# Microcontroller.net
KiCad netlist of a schematic drawn in Altium Designer
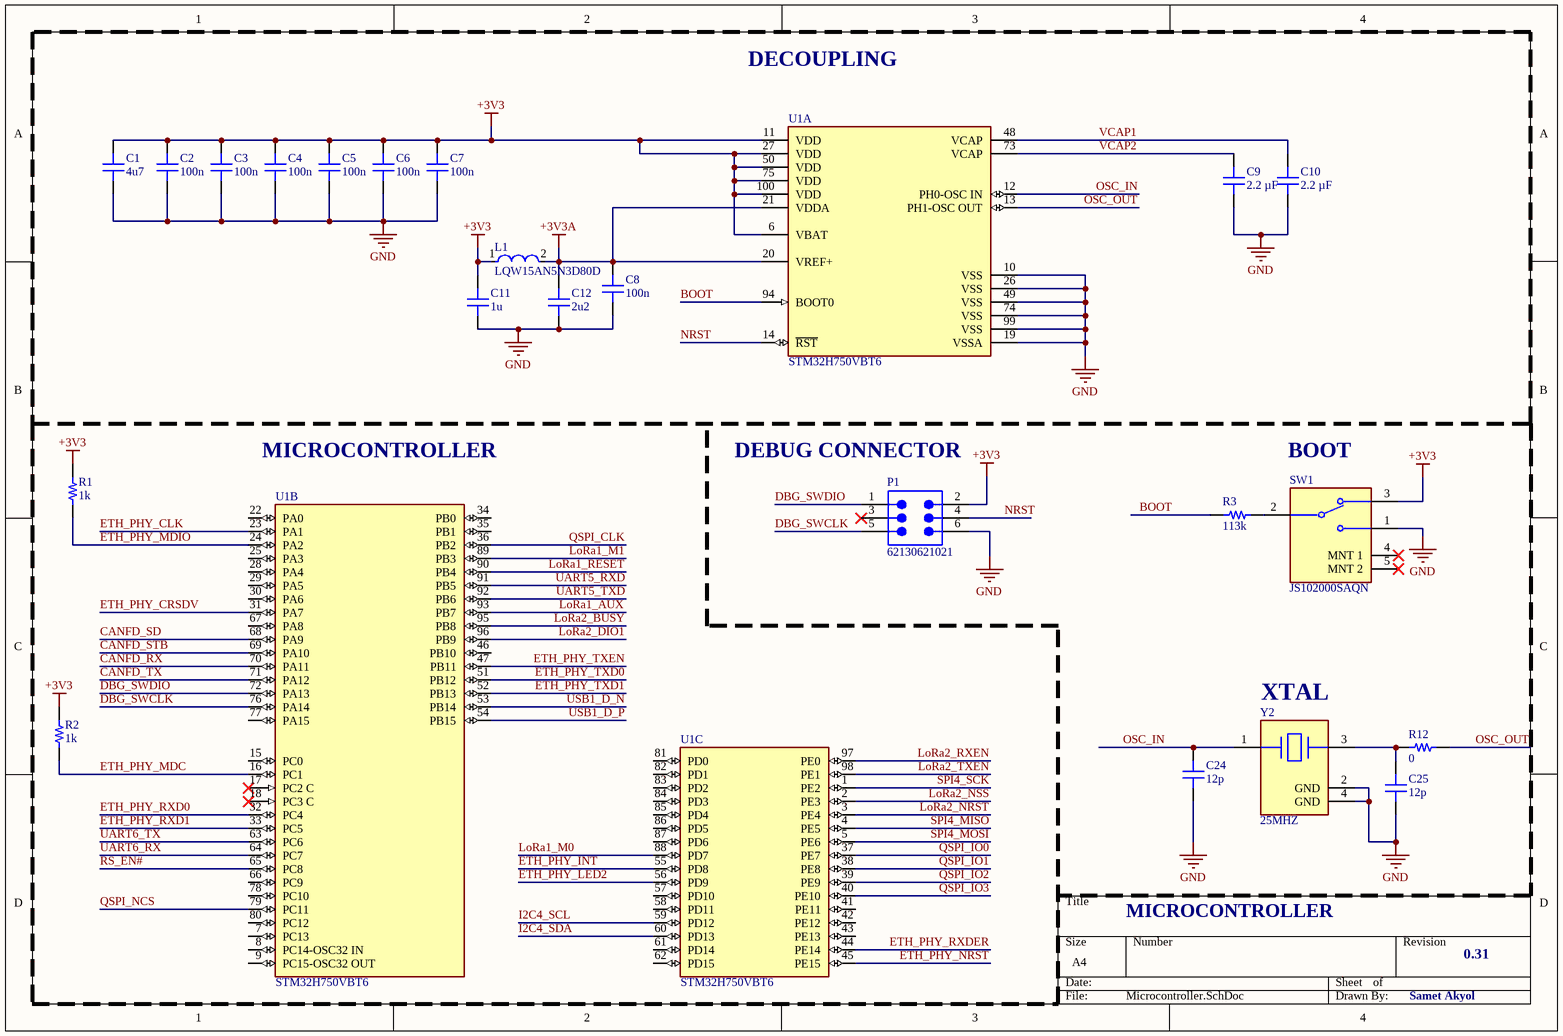
[diagram p0: Microcontroller.SchDoc]

(export (version "E")
  (design (tool "Eeschema 10.0.6"))
  (components
    (comp (ref "C1")
      (value "4u7")
      (footprint "CAP 0402_1005")
      (description "CAP CER 100NF 10V X7R 0402")
      (fields
        (field (name "PART NUMBER") "CL05B104KP5VPNC")
        (field (name "MANUFACTURER") "Samsung Electro-Mechanics")
      )
      (libsource (lib "Celestial Altium Library - altium_library") (part "Capacitor"))
    )
    (comp (ref "C2")
      (value "100n")
      (footprint "CAP 0402_1005")
      (description "CAP CER 100NF 10V X7R 0402")
      (fields
        (field (name "PART NUMBER") "CL05B104KP5VPNC")
        (field (name "MANUFACTURER") "Samsung Electro-Mechanics")
      )
      (libsource (lib "Celestial Altium Library - altium_library") (part "Capacitor"))
    )
    (comp (ref "C3")
      (value "100n")
      (footprint "CAP 0402_1005")
      (description "CAP CER 100NF 10V X7R 0402")
      (fields
        (field (name "PART NUMBER") "CL05B104KP5VPNC")
        (field (name "MANUFACTURER") "Samsung Electro-Mechanics")
      )
      (libsource (lib "Celestial Altium Library - altium_library") (part "Capacitor"))
    )
    (comp (ref "C4")
      (value "100n")
      (footprint "CAP 0402_1005")
      (description "CAP CER 100NF 10V X7R 0402")
      (fields
        (field (name "PART NUMBER") "CL05B104KP5VPNC")
        (field (name "MANUFACTURER") "Samsung Electro-Mechanics")
      )
      (libsource (lib "Celestial Altium Library - altium_library") (part "Capacitor"))
    )
    (comp (ref "C5")
      (value "100n")
      (footprint "CAP 0402_1005")
      (description "CAP CER 100NF 10V X7R 0402")
      (fields
        (field (name "PART NUMBER") "CL05B104KP5VPNC")
        (field (name "MANUFACTURER") "Samsung Electro-Mechanics")
      )
      (libsource (lib "Celestial Altium Library - altium_library") (part "Capacitor"))
    )
    (comp (ref "C6")
      (value "100n")
      (footprint "CAP 0402_1005")
      (description "CAP CER 100NF 10V X7R 0402")
      (fields
        (field (name "PART NUMBER") "CL05B104KP5VPNC")
        (field (name "MANUFACTURER") "Samsung Electro-Mechanics")
      )
      (libsource (lib "Celestial Altium Library - altium_library") (part "Capacitor"))
    )
    (comp (ref "C7")
      (value "100n")
      (footprint "CAP 0402_1005")
      (description "CAP CER 100NF 10V X7R 0402")
      (fields
        (field (name "PART NUMBER") "CL05B104KP5VPNC")
        (field (name "MANUFACTURER") "Samsung Electro-Mechanics")
      )
      (libsource (lib "Celestial Altium Library - altium_library") (part "Capacitor"))
    )
    (comp (ref "C8")
      (value "100n")
      (footprint "CAP 0402_1005")
      (description "CAP CER 100NF 10V X7R 0402")
      (fields
        (field (name "PART NUMBER") "CL05B104KP5VPNC")
        (field (name "MANUFACTURER") "Samsung Electro-Mechanics")
      )
      (libsource (lib "Celestial Altium Library - altium_library") (part "Capacitor"))
    )
    (comp (ref "C9")
      (value "2.2 µF")
      (footprint "CAP 0402_1005")
      (description "CAP CER 2.2UF 16V X5R 0402")
      (fields
        (field (name "PART NUMBER") "CL05A225KO5NQNC")
        (field (name "MANUFACTURER") "Samsung Electro-Mechanics")
      )
      (libsource (lib "Celestial Altium Library - altium_library") (part "Capacitor"))
    )
    (comp (ref "C10")
      (value "2.2 µF")
      (footprint "CAP 0402_1005")
      (description "CAP CER 2.2UF 16V X5R 0402")
      (fields
        (field (name "PART NUMBER") "CL05A225KO5NQNC")
        (field (name "MANUFACTURER") "Samsung Electro-Mechanics")
      )
      (libsource (lib "Celestial Altium Library - altium_library") (part "Capacitor"))
    )
    (comp (ref "C11")
      (value "1u")
      (footprint "CAP 0402_1005")
      (description "CAP CER 100NF 10V X7R 0402")
      (fields
        (field (name "PART NUMBER") "CL05B104KP5VPNC")
        (field (name "MANUFACTURER") "Samsung Electro-Mechanics")
      )
      (libsource (lib "Celestial Altium Library - altium_library") (part "Capacitor"))
    )
    (comp (ref "C12")
      (value "2u2")
      (footprint "CAP 0402_1005")
      (description "CAP CER 100NF 10V X7R 0402")
      (fields
        (field (name "PART NUMBER") "CL05B104KP5VPNC")
        (field (name "MANUFACTURER") "Samsung Electro-Mechanics")
      )
      (libsource (lib "Celestial Altium Library - altium_library") (part "Capacitor"))
    )
    (comp (ref "C24")
      (value "12p")
      (footprint "CAP 0402_1005")
      (description "CAP CER 100NF 10V X7R 0402")
      (fields
        (field (name "PART NUMBER") "CL05B104KP5VPNC")
        (field (name "MANUFACTURER") "Samsung Electro-Mechanics")
      )
      (libsource (lib "Celestial Altium Library - altium_library") (part "Capacitor"))
    )
    (comp (ref "C25")
      (value "12p")
      (footprint "CAP 0402_1005")
      (description "CAP CER 100NF 10V X7R 0402")
      (fields
        (field (name "PART NUMBER") "CL05B104KP5VPNC")
        (field (name "MANUFACTURER") "Samsung Electro-Mechanics")
      )
      (libsource (lib "Celestial Altium Library - altium_library") (part "Capacitor"))
    )
    (comp (ref "L1")
      (value "LQW15AN5N3D80D")
      (footprint "FP-LQW15AN_80-MFG")
      (description "Wire Wound RF Inductor 5.3nH ±0.5nH 1770mA 0.04Ω 0402 (1005)")
      (libsource (lib "Altium Content Vault") (part "725321dda6339637d4d059423bc1c3c"))
    )
    (comp (ref "P1")
      (value "62130621021")
      (footprint "62130621021")
      (libsource (lib "Altium Content Vault") (part "Header_Male_2R_06P"))
    )
    (comp (ref "R1")
      (value "1k")
      (footprint "RES 0402_1005")
      (description "RES 249K OHM 0.1% 1/10W 0402")
      (fields
        (field (name "PART NUMBER") "RP73PF1E249KBTD")
        (field (name "MANUFACTURER") "TE Connectivity Passive Product")
      )
      (libsource (lib "Celestial Altium Library - altium_library") (part "Resistor"))
    )
    (comp (ref "R2")
      (value "1k")
      (footprint "RES 0402_1005")
      (description "RES 249K OHM 0.1% 1/10W 0402")
      (fields
        (field (name "PART NUMBER") "RP73PF1E249KBTD")
        (field (name "MANUFACTURER") "TE Connectivity Passive Product")
      )
      (libsource (lib "Celestial Altium Library - altium_library") (part "Resistor"))
    )
    (comp (ref "R3")
      (value "113k")
      (footprint "RES 0402_1005")
      (description "RES 249K OHM 0.1% 1/10W 0402")
      (fields
        (field (name "PART NUMBER") "RP73PF1E249KBTD")
        (field (name "MANUFACTURER") "TE Connectivity Passive Product")
      )
      (libsource (lib "Celestial Altium Library - altium_library") (part "Resistor"))
    )
    (comp (ref "R12")
      (value "0")
      (footprint "RES 0402_1005")
      (description "RES 249K OHM 0.1% 1/10W 0402")
      (fields
        (field (name "PART NUMBER") "RP73PF1E249KBTD")
        (field (name "MANUFACTURER") "TE Connectivity Passive Product")
      )
      (libsource (lib "Celestial Altium Library - altium_library") (part "Resistor"))
    )
    (comp (ref "SW1")
      (value "JS102000SAQN")
      (footprint "FP-JS102000SAQN-MFG")
      (description "SWITCH SLIDE SPDT 1MA 5V")
      (libsource (lib "Altium Content Vault") (part "6887e5fe807d9c5c2853bed39bc55bf"))
    )
    (comp (ref "U1")
      (value "STM32H750VBT6")
      (footprint "FP-LQFP100-1L-MFG")
      (description "IC MCU 32BIT 128KB FLASH 100LQFP")
      (fields
        (field (name "OCTOPART") "https://octopart.com/stm32h750vbt6-stmicroelectronics-94048547")
        (field (name "MANUFACTURER") "STMicroelectronics")
      )
      (libsource (lib "Altium Content Vault") (part "aca449acb2b80670ba40d015d68dc7a"))
    )
    (comp (ref "Y2")
      (value "25MHZ")
      (footprint "FP-ABM8G-MFG")
      (description "Crystal 25MHz ±20ppm (Tol) ±30ppm (Stability) 18pF FUND 60Ω 4-Pin SMD T/R")
      (fields (field (name "TOLERANCE") "20ppm"))
      (libsource (lib "Altium Content Vault") (part "48e526d86b7f2615d98721063c72f49"))
    )
  )
  (nets
    (net (code "1") (name "+3V3") (class "Default")
      (node (ref "C1") (pin "2") (pinfunction "2_2") (pintype "passive"))
      (node (ref "C11") (pin "2") (pinfunction "2_2") (pintype "passive"))
      (node (ref "C2") (pin "2") (pinfunction "2_2") (pintype "passive"))
      (node (ref "C3") (pin "2") (pinfunction "2_2") (pintype "passive"))
      (node (ref "C4") (pin "2") (pinfunction "2_2") (pintype "passive"))
      (node (ref "C5") (pin "2") (pinfunction "2_2") (pintype "passive"))
      (node (ref "C6") (pin "2") (pinfunction "2_2") (pintype "passive"))
      (node (ref "C7") (pin "2") (pinfunction "2_2") (pintype "passive"))
      (node (ref "L1") (pin "1") (pinfunction "1_1") (pintype "passive"))
      (node (ref "P1") (pin "2") (pinfunction "2_2") (pintype "passive"))
      (node (ref "R1") (pin "1") (pinfunction "1_1") (pintype "passive"))
      (node (ref "R2") (pin "1") (pinfunction "1_1") (pintype "passive"))
      (node (ref "SW1") (pin "3") (pinfunction "3_3") (pintype "passive"))
      (node (ref "U1") (pin "100") (pinfunction "VDD_100") (pintype "power_in"))
      (node (ref "U1") (pin "11") (pinfunction "VDD_11") (pintype "power_in"))
      (node (ref "U1") (pin "27") (pinfunction "VDD_27") (pintype "power_in"))
      (node (ref "U1") (pin "50") (pinfunction "VDD_50") (pintype "power_in"))
      (node (ref "U1") (pin "6") (pinfunction "VBAT_6") (pintype "power_in"))
      (node (ref "U1") (pin "75") (pinfunction "VDD_75") (pintype "power_in"))
    )
    (net (code "2") (name "+3V3A") (class "Default")
      (node (ref "C12") (pin "2") (pinfunction "2_2") (pintype "passive"))
      (node (ref "C8") (pin "2") (pinfunction "2_2") (pintype "passive"))
      (node (ref "L1") (pin "2") (pinfunction "2_2") (pintype "passive"))
      (node (ref "U1") (pin "20") (pinfunction "VREF+_20") (pintype "power_in"))
      (node (ref "U1") (pin "21") (pinfunction "VDDA_21") (pintype "power_in"))
    )
    (net (code "3") (name "/BOOT") (class "Default")
      (node (ref "R3") (pin "2") (pinfunction "2_2") (pintype "passive"))
      (node (ref "U1") (pin "94") (pinfunction "BOOT0_94") (pintype "input"))
    )
    (net (code "4") (name "/CANFD_RX") (class "Default")
      (node (ref "U1") (pin "70") (pinfunction "PA11_70") (pintype "bidirectional"))
    )
    (net (code "5") (name "/CANFD_SD") (class "Default")
      (node (ref "U1") (pin "68") (pinfunction "PA9_68") (pintype "bidirectional"))
    )
    (net (code "6") (name "/CANFD_STB") (class "Default")
      (node (ref "U1") (pin "69") (pinfunction "PA10_69") (pintype "bidirectional"))
    )
    (net (code "7") (name "/CANFD_TX") (class "Default")
      (node (ref "U1") (pin "71") (pinfunction "PA12_71") (pintype "bidirectional"))
    )
    (net (code "8") (name "/DBG_SWCLK") (class "Default")
      (node (ref "P1") (pin "5") (pinfunction "5_5") (pintype "passive"))
      (node (ref "U1") (pin "76") (pinfunction "PA14_76") (pintype "bidirectional"))
    )
    (net (code "9") (name "/DBG_SWDIO") (class "Default")
      (node (ref "P1") (pin "1") (pinfunction "1_1") (pintype "passive"))
      (node (ref "U1") (pin "72") (pinfunction "PA13_72") (pintype "bidirectional"))
    )
    (net (code "10") (name "/ETH_PHY_CLK") (class "Default")
      (node (ref "U1") (pin "23") (pinfunction "PA1_23") (pintype "bidirectional"))
    )
    (net (code "11") (name "/ETH_PHY_CRSDV") (class "Default")
      (node (ref "U1") (pin "31") (pinfunction "PA7_31") (pintype "bidirectional"))
    )
    (net (code "12") (name "/ETH_PHY_INT") (class "Default")
      (node (ref "U1") (pin "55") (pinfunction "PD8_55") (pintype "bidirectional"))
    )
    (net (code "13") (name "/ETH_PHY_LED2") (class "Default")
      (node (ref "U1") (pin "56") (pinfunction "PD9_56") (pintype "bidirectional"))
    )
    (net (code "14") (name "/ETH_PHY_MDC") (class "Default")
      (node (ref "R2") (pin "2") (pinfunction "2_2") (pintype "passive"))
      (node (ref "U1") (pin "16") (pinfunction "PC1_16") (pintype "bidirectional"))
    )
    (net (code "15") (name "/ETH_PHY_MDIO") (class "Default")
      (node (ref "R1") (pin "2") (pinfunction "2_2") (pintype "passive"))
      (node (ref "U1") (pin "24") (pinfunction "PA2_24") (pintype "bidirectional"))
    )
    (net (code "16") (name "/ETH_PHY_NRST") (class "Default")
      (node (ref "U1") (pin "45") (pinfunction "PE15_45") (pintype "bidirectional"))
    )
    (net (code "17") (name "/ETH_PHY_RXD0") (class "Default")
      (node (ref "U1") (pin "32") (pinfunction "PC4_32") (pintype "bidirectional"))
    )
    (net (code "18") (name "/ETH_PHY_RXD1") (class "Default")
      (node (ref "U1") (pin "33") (pinfunction "PC5_33") (pintype "bidirectional"))
    )
    (net (code "19") (name "/ETH_PHY_RXDER") (class "Default")
      (node (ref "U1") (pin "44") (pinfunction "PE14_44") (pintype "bidirectional"))
    )
    (net (code "20") (name "/ETH_PHY_TXD0") (class "Default")
      (node (ref "U1") (pin "51") (pinfunction "PB12_51") (pintype "bidirectional"))
    )
    (net (code "21") (name "/ETH_PHY_TXD1") (class "Default")
      (node (ref "U1") (pin "52") (pinfunction "PB13_52") (pintype "bidirectional"))
    )
    (net (code "22") (name "/ETH_PHY_TXEN") (class "Default")
      (node (ref "U1") (pin "47") (pinfunction "PB11_47") (pintype "bidirectional"))
    )
    (net (code "23") (name "/I2C4_SCL") (class "Default")
      (node (ref "U1") (pin "59") (pinfunction "PD12_59") (pintype "bidirectional"))
    )
    (net (code "24") (name "/I2C4_SDA") (class "Default")
      (node (ref "U1") (pin "60") (pinfunction "PD13_60") (pintype "bidirectional"))
    )
    (net (code "25") (name "/LoRa1_AUX") (class "Default")
      (node (ref "U1") (pin "93") (pinfunction "PB7_93") (pintype "bidirectional"))
    )
    (net (code "26") (name "/LoRa1_M0") (class "Default")
      (node (ref "U1") (pin "88") (pinfunction "PD7_88") (pintype "bidirectional"))
    )
    (net (code "27") (name "/LoRa1_M1") (class "Default")
      (node (ref "U1") (pin "89") (pinfunction "PB3_89") (pintype "bidirectional"))
    )
    (net (code "28") (name "/LoRa1_RESET") (class "Default")
      (node (ref "U1") (pin "90") (pinfunction "PB4_90") (pintype "bidirectional"))
    )
    (net (code "29") (name "/LoRa2_BUSY") (class "Default")
      (node (ref "U1") (pin "95") (pinfunction "PB8_95") (pintype "bidirectional"))
    )
    (net (code "30") (name "/LoRa2_DIO1") (class "Default")
      (node (ref "U1") (pin "96") (pinfunction "PB9_96") (pintype "bidirectional"))
    )
    (net (code "31") (name "/LoRa2_NRST") (class "Default")
      (node (ref "U1") (pin "3") (pinfunction "PE4_3") (pintype "bidirectional"))
    )
    (net (code "32") (name "/LoRa2_NSS") (class "Default")
      (node (ref "U1") (pin "2") (pinfunction "PE3_2") (pintype "bidirectional"))
    )
    (net (code "33") (name "/LoRa2_RXEN") (class "Default")
      (node (ref "U1") (pin "97") (pinfunction "PE0_97") (pintype "bidirectional"))
    )
    (net (code "34") (name "/LoRa2_TXEN") (class "Default")
      (node (ref "U1") (pin "98") (pinfunction "PE1_98") (pintype "bidirectional"))
    )
    (net (code "35") (name "/NRST") (class "Default")
      (node (ref "P1") (pin "4") (pinfunction "4_4") (pintype "passive"))
      (node (ref "U1") (pin "14") (pinfunction "~{RST}_14") (pintype "bidirectional"))
    )
    (net (code "36") (name "/OSC_IN") (class "Default")
      (node (ref "C24") (pin "2") (pinfunction "2_2") (pintype "passive"))
      (node (ref "U1") (pin "12") (pinfunction "PH0-OSC_IN_12") (pintype "bidirectional"))
      (node (ref "Y2") (pin "1") (pinfunction "1_1") (pintype "passive"))
    )
    (net (code "37") (name "/OSC_OUT") (class "Default")
      (node (ref "R12") (pin "1") (pinfunction "1_1") (pintype "passive"))
      (node (ref "U1") (pin "13") (pinfunction "PH1-OSC_OUT_13") (pintype "bidirectional"))
    )
    (net (code "38") (name "/QSPI_CLK") (class "Default")
      (node (ref "U1") (pin "36") (pinfunction "PB2_36") (pintype "bidirectional"))
    )
    (net (code "39") (name "/QSPI_IO0") (class "Default")
      (node (ref "U1") (pin "37") (pinfunction "PE7_37") (pintype "bidirectional"))
    )
    (net (code "40") (name "/QSPI_IO1") (class "Default")
      (node (ref "U1") (pin "38") (pinfunction "PE8_38") (pintype "bidirectional"))
    )
    (net (code "41") (name "/QSPI_IO2") (class "Default")
      (node (ref "U1") (pin "39") (pinfunction "PE9_39") (pintype "bidirectional"))
    )
    (net (code "42") (name "/QSPI_IO3") (class "Default")
      (node (ref "U1") (pin "40") (pinfunction "PE10_40") (pintype "bidirectional"))
    )
    (net (code "43") (name "/QSPI_NCS") (class "Default")
      (node (ref "U1") (pin "79") (pinfunction "PC11_79") (pintype "bidirectional"))
    )
    (net (code "44") (name "/RS_EN#") (class "Default")
      (node (ref "U1") (pin "65") (pinfunction "PC8_65") (pintype "bidirectional"))
    )
    (net (code "45") (name "/SPI4_MISO") (class "Default")
      (node (ref "U1") (pin "4") (pinfunction "PE5_4") (pintype "bidirectional"))
    )
    (net (code "46") (name "/SPI4_MOSI") (class "Default")
      (node (ref "U1") (pin "5") (pinfunction "PE6_5") (pintype "bidirectional"))
    )
    (net (code "47") (name "/SPI4_SCK") (class "Default")
      (node (ref "U1") (pin "1") (pinfunction "PE2_1") (pintype "bidirectional"))
    )
    (net (code "48") (name "/UART5_RXD") (class "Default")
      (node (ref "U1") (pin "91") (pinfunction "PB5_91") (pintype "bidirectional"))
    )
    (net (code "49") (name "/UART5_TXD") (class "Default")
      (node (ref "U1") (pin "92") (pinfunction "PB6_92") (pintype "bidirectional"))
    )
    (net (code "50") (name "/UART6_RX") (class "Default")
      (node (ref "U1") (pin "64") (pinfunction "PC7_64") (pintype "bidirectional"))
    )
    (net (code "51") (name "/UART6_TX") (class "Default")
      (node (ref "U1") (pin "63") (pinfunction "PC6_63") (pintype "bidirectional"))
    )
    (net (code "52") (name "/USB1_D_N") (class "Default")
      (node (ref "U1") (pin "53") (pinfunction "PB14_53") (pintype "bidirectional"))
    )
    (net (code "53") (name "/USB1_D_P") (class "Default")
      (node (ref "U1") (pin "54") (pinfunction "PB15_54") (pintype "bidirectional"))
    )
    (net (code "54") (name "/VCAP1") (class "Default")
      (node (ref "C10") (pin "2") (pinfunction "2_2") (pintype "passive"))
      (node (ref "U1") (pin "48") (pinfunction "VCAP_48") (pintype "power_in"))
    )
    (net (code "55") (name "/VCAP2") (class "Default")
      (node (ref "C9") (pin "2") (pinfunction "2_2") (pintype "passive"))
      (node (ref "U1") (pin "73") (pinfunction "VCAP_73") (pintype "power_in"))
    )
    (net (code "56") (name "GND") (class "Default")
      (node (ref "C1") (pin "1") (pinfunction "1_1") (pintype "passive"))
      (node (ref "C10") (pin "1") (pinfunction "1_1") (pintype "passive"))
      (node (ref "C11") (pin "1") (pinfunction "1_1") (pintype "passive"))
      (node (ref "C12") (pin "1") (pinfunction "1_1") (pintype "passive"))
      (node (ref "C2") (pin "1") (pinfunction "1_1") (pintype "passive"))
      (node (ref "C24") (pin "1") (pinfunction "1_1") (pintype "passive"))
      (node (ref "C25") (pin "1") (pinfunction "1_1") (pintype "passive"))
      (node (ref "C3") (pin "1") (pinfunction "1_1") (pintype "passive"))
      (node (ref "C4") (pin "1") (pinfunction "1_1") (pintype "passive"))
      (node (ref "C5") (pin "1") (pinfunction "1_1") (pintype "passive"))
      (node (ref "C6") (pin "1") (pinfunction "1_1") (pintype "passive"))
      (node (ref "C7") (pin "1") (pinfunction "1_1") (pintype "passive"))
      (node (ref "C8") (pin "1") (pinfunction "1_1") (pintype "passive"))
      (node (ref "C9") (pin "1") (pinfunction "1_1") (pintype "passive"))
      (node (ref "P1") (pin "6") (pinfunction "6_6") (pintype "passive"))
      (node (ref "SW1") (pin "1") (pinfunction "1_1") (pintype "passive"))
      (node (ref "U1") (pin "10") (pinfunction "VSS_10") (pintype "power_in"))
      (node (ref "U1") (pin "19") (pinfunction "VSSA_19") (pintype "power_in"))
      (node (ref "U1") (pin "26") (pinfunction "VSS_26") (pintype "power_in"))
      (node (ref "U1") (pin "49") (pinfunction "VSS_49") (pintype "power_in"))
      (node (ref "U1") (pin "74") (pinfunction "VSS_74") (pintype "power_in"))
      (node (ref "U1") (pin "99") (pinfunction "VSS_99") (pintype "power_in"))
      (node (ref "Y2") (pin "2") (pinfunction "GND_2") (pintype "power_in"))
      (node (ref "Y2") (pin "4") (pinfunction "GND_4") (pintype "power_in"))
    )
    (net (code "57") (name "Net-(C25-Pad2)") (class "Default")
      (node (ref "C25") (pin "2") (pinfunction "2_2") (pintype "passive"))
      (node (ref "R12") (pin "2") (pinfunction "2_2") (pintype "passive"))
      (node (ref "Y2") (pin "3") (pinfunction "3_3") (pintype "passive"))
    )
    (net (code "58") (name "Net-(SW1-C)") (class "Default")
      (node (ref "R3") (pin "1") (pinfunction "1_1") (pintype "passive"))
      (node (ref "SW1") (pin "2") (pinfunction "C_2") (pintype "passive"))
    )
    (net (code "59") (name "unconnected-(P1-Pad3)") (class "Default")
      (node (ref "P1") (pin "3") (pinfunction "3_3") (pintype "passive+no_connect"))
    )
    (net (code "60") (name "unconnected-(SW1-MNT_1-Pad4)") (class "Default")
      (node (ref "SW1") (pin "4") (pinfunction "MNT_1_4") (pintype "passive+no_connect"))
    )
    (net (code "61") (name "unconnected-(SW1-MNT_2-Pad5)") (class "Default")
      (node (ref "SW1") (pin "5") (pinfunction "MNT_2_5") (pintype "passive+no_connect"))
    )
    (net (code "62") (name "unconnected-(U1B-PA0-Pad22)") (class "Default")
      (node (ref "U1") (pin "22") (pinfunction "PA0_22") (pintype "bidirectional"))
    )
    (net (code "63") (name "unconnected-(U1B-PA3-Pad25)") (class "Default")
      (node (ref "U1") (pin "25") (pinfunction "PA3_25") (pintype "bidirectional"))
    )
    (net (code "64") (name "unconnected-(U1B-PA4-Pad28)") (class "Default")
      (node (ref "U1") (pin "28") (pinfunction "PA4_28") (pintype "bidirectional"))
    )
    (net (code "65") (name "unconnected-(U1B-PA5-Pad29)") (class "Default")
      (node (ref "U1") (pin "29") (pinfunction "PA5_29") (pintype "bidirectional"))
    )
    (net (code "66") (name "unconnected-(U1B-PA6-Pad30)") (class "Default")
      (node (ref "U1") (pin "30") (pinfunction "PA6_30") (pintype "bidirectional"))
    )
    (net (code "67") (name "unconnected-(U1B-PA8-Pad67)") (class "Default")
      (node (ref "U1") (pin "67") (pinfunction "PA8_67") (pintype "bidirectional"))
    )
    (net (code "68") (name "unconnected-(U1B-PA15-Pad77)") (class "Default")
      (node (ref "U1") (pin "77") (pinfunction "PA15_77") (pintype "bidirectional"))
    )
    (net (code "69") (name "unconnected-(U1B-PB0-Pad34)") (class "Default")
      (node (ref "U1") (pin "34") (pinfunction "PB0_34") (pintype "bidirectional"))
    )
    (net (code "70") (name "unconnected-(U1B-PB1-Pad35)") (class "Default")
      (node (ref "U1") (pin "35") (pinfunction "PB1_35") (pintype "bidirectional"))
    )
    (net (code "71") (name "unconnected-(U1B-PB10-Pad46)") (class "Default")
      (node (ref "U1") (pin "46") (pinfunction "PB10_46") (pintype "bidirectional"))
    )
    (net (code "72") (name "unconnected-(U1B-PC0-Pad15)") (class "Default")
      (node (ref "U1") (pin "15") (pinfunction "PC0_15") (pintype "bidirectional"))
    )
    (net (code "73") (name "unconnected-(U1B-PC2_C-Pad17)") (class "Default")
      (node (ref "U1") (pin "17") (pinfunction "PC2_C_17") (pintype "input+no_connect"))
    )
    (net (code "74") (name "unconnected-(U1B-PC3_C-Pad18)") (class "Default")
      (node (ref "U1") (pin "18") (pinfunction "PC3_C_18") (pintype "input+no_connect"))
    )
    (net (code "75") (name "unconnected-(U1B-PC9-Pad66)") (class "Default")
      (node (ref "U1") (pin "66") (pinfunction "PC9_66") (pintype "bidirectional"))
    )
    (net (code "76") (name "unconnected-(U1B-PC10-Pad78)") (class "Default")
      (node (ref "U1") (pin "78") (pinfunction "PC10_78") (pintype "bidirectional"))
    )
    (net (code "77") (name "unconnected-(U1B-PC12-Pad80)") (class "Default")
      (node (ref "U1") (pin "80") (pinfunction "PC12_80") (pintype "bidirectional"))
    )
    (net (code "78") (name "unconnected-(U1B-PC13-Pad7)") (class "Default")
      (node (ref "U1") (pin "7") (pinfunction "PC13_7") (pintype "bidirectional"))
    )
    (net (code "79") (name "unconnected-(U1B-PC14-OSC32_IN-Pad8)") (class "Default")
      (node (ref "U1") (pin "8") (pinfunction "PC14-OSC32_IN_8") (pintype "bidirectional"))
    )
    (net (code "80") (name "unconnected-(U1B-PC15-OSC32_OUT-Pad9)") (class "Default")
      (node (ref "U1") (pin "9") (pinfunction "PC15-OSC32_OUT_9") (pintype "bidirectional"))
    )
    (net (code "81") (name "unconnected-(U1C-PD0-Pad81)") (class "Default")
      (node (ref "U1") (pin "81") (pinfunction "PD0_81") (pintype "bidirectional"))
    )
    (net (code "82") (name "unconnected-(U1C-PD1-Pad82)") (class "Default")
      (node (ref "U1") (pin "82") (pinfunction "PD1_82") (pintype "bidirectional"))
    )
    (net (code "83") (name "unconnected-(U1C-PD2-Pad83)") (class "Default")
      (node (ref "U1") (pin "83") (pinfunction "PD2_83") (pintype "bidirectional"))
    )
    (net (code "84") (name "unconnected-(U1C-PD3-Pad84)") (class "Default")
      (node (ref "U1") (pin "84") (pinfunction "PD3_84") (pintype "bidirectional"))
    )
    (net (code "85") (name "unconnected-(U1C-PD4-Pad85)") (class "Default")
      (node (ref "U1") (pin "85") (pinfunction "PD4_85") (pintype "bidirectional"))
    )
    (net (code "86") (name "unconnected-(U1C-PD5-Pad86)") (class "Default")
      (node (ref "U1") (pin "86") (pinfunction "PD5_86") (pintype "bidirectional"))
    )
    (net (code "87") (name "unconnected-(U1C-PD6-Pad87)") (class "Default")
      (node (ref "U1") (pin "87") (pinfunction "PD6_87") (pintype "bidirectional"))
    )
    (net (code "88") (name "unconnected-(U1C-PD10-Pad57)") (class "Default")
      (node (ref "U1") (pin "57") (pinfunction "PD10_57") (pintype "bidirectional"))
    )
    (net (code "89") (name "unconnected-(U1C-PD11-Pad58)") (class "Default")
      (node (ref "U1") (pin "58") (pinfunction "PD11_58") (pintype "bidirectional"))
    )
    (net (code "90") (name "unconnected-(U1C-PD14-Pad61)") (class "Default")
      (node (ref "U1") (pin "61") (pinfunction "PD14_61") (pintype "bidirectional"))
    )
    (net (code "91") (name "unconnected-(U1C-PD15-Pad62)") (class "Default")
      (node (ref "U1") (pin "62") (pinfunction "PD15_62") (pintype "bidirectional"))
    )
    (net (code "92") (name "unconnected-(U1C-PE11-Pad41)") (class "Default")
      (node (ref "U1") (pin "41") (pinfunction "PE11_41") (pintype "bidirectional"))
    )
    (net (code "93") (name "unconnected-(U1C-PE12-Pad42)") (class "Default")
      (node (ref "U1") (pin "42") (pinfunction "PE12_42") (pintype "bidirectional"))
    )
    (net (code "94") (name "unconnected-(U1C-PE13-Pad43)") (class "Default")
      (node (ref "U1") (pin "43") (pinfunction "PE13_43") (pintype "bidirectional"))
    )
  )
)
